# IO_Converter.net
KiCad netlist of a schematic drawn in Altium Designer
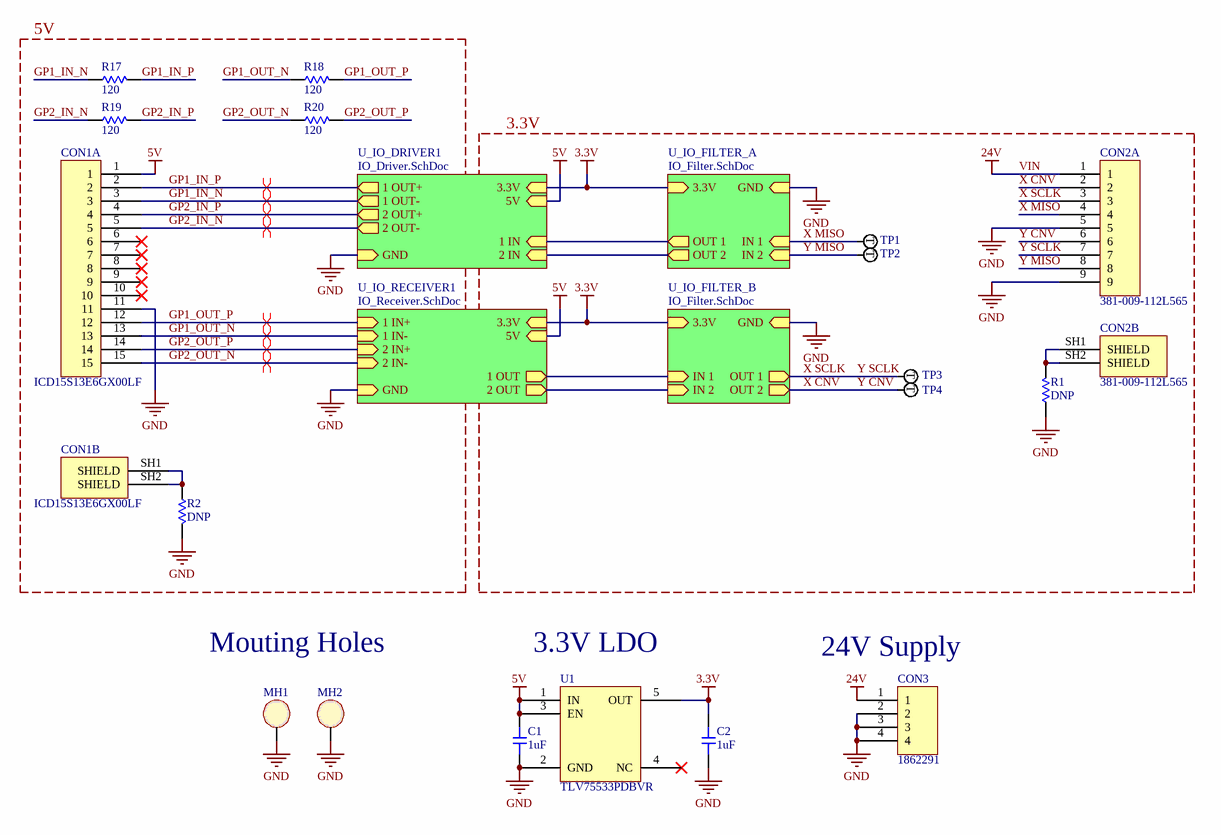
[diagram p0: IO_Converter.SchDoc]

(export (version "E")
  (design (tool "Eeschema 10.0.6"))
  (components
    (comp (ref "C1")
      (value "1uF")
      (footprint "0603-CAP")
      (description "CAP CER 1UF 10V X5R 0603")
      (fields (field (name "Comment") "CL10A105KP8NNWC"))
      (libsource (lib "IO_Converter") (part "Capacitor 1uF"))
    )
    (comp (ref "C2")
      (value "1uF")
      (footprint "0603-CAP")
      (description "CAP CER 1UF 10V X5R 0603")
      (fields (field (name "Comment") "CL10A105KP8NNWC"))
      (libsource (lib "IO_Converter") (part "Capacitor 1uF"))
    )
    (comp (ref "CON1")
      (value "ICD15S13E6GX00LF")
      (footprint "ICD15S13E6GX00LF")
      (description "15 Position D-Sub, High Density Receptacle, Female Sockets Connector")
      (libsource (lib "CRAMB") (part "ICD15S13E6GX00LF"))
    )
    (comp (ref "CON2")
      (value "381-009-112L565")
      (footprint "381-009-112L565")
      (description "9 Position D-Type, Micro-D Plug, Male Pins Connector")
      (libsource (lib "IO_Converter") (part "381-009-112L565"))
    )
    (comp (ref "CON3")
      (value "1862291")
      (footprint "1862291")
      (description "TERM BLOCK 4POS 45DEG 5MM PCB")
      (libsource (lib "IO_Converter") (part "1862291"))
    )
    (comp (ref "MH1")
      (value "MOUNT_HOLE")
      (footprint "MOUNTING_HOLE")
      (description "MOUNTING HOLE")
      (libsource (lib "IO_Converter") (part "MOUNT_HOLE"))
    )
    (comp (ref "MH2")
      (value "MOUNT_HOLE")
      (footprint "MOUNTING_HOLE")
      (description "MOUNTING HOLE")
      (libsource (lib "IO_Converter") (part "MOUNT_HOLE"))
    )
    (comp (ref "R1")
      (value "DNP")
      (footprint "0603-RES")
      (fields (field (name "Comment") "Resistor"))
      (libsource (lib "CRAMB") (part "Resistor"))
    )
    (comp (ref "R2")
      (value "DNP")
      (footprint "0603-RES")
      (fields (field (name "Comment") "Resistor"))
      (libsource (lib "CRAMB") (part "Resistor"))
    )
    (comp (ref "R17")
      (value "120")
      (footprint "0603-RES")
      (description "RES 120 OHM 5% 1/10W 0603")
      (fields (field (name "MANUFACTURER PART NUMBER") "RMCF0603JT120R"))
      (libsource (lib "IO_Converter") (part "Resistor"))
    )
    (comp (ref "R18")
      (value "120")
      (footprint "0603-RES")
      (description "RES 120 OHM 5% 1/10W 0603")
      (fields (field (name "MANUFACTURER PART NUMBER") "RMCF0603JT120R"))
      (libsource (lib "IO_Converter") (part "Resistor"))
    )
    (comp (ref "R19")
      (value "120")
      (footprint "0603-RES")
      (description "RES 120 OHM 5% 1/10W 0603")
      (fields (field (name "MANUFACTURER PART NUMBER") "RMCF0603JT120R"))
      (libsource (lib "IO_Converter") (part "Resistor"))
    )
    (comp (ref "R20")
      (value "120")
      (footprint "0603-RES")
      (description "RES 120 OHM 5% 1/10W 0603")
      (fields (field (name "Comment") "RMCF0603JT120R"))
      (libsource (lib "IO_Converter") (part "Resistor"))
    )
    (comp (ref "TP1")
      (value "RCU-0C")
      (footprint "RCU-0C")
      (description "PC TEST POINT NATURAL")
      (libsource (lib "IO_Converter") (part "Test Point"))
    )
    (comp (ref "TP2")
      (value "RCU-0C")
      (footprint "RCU-0C")
      (description "PC TEST POINT NATURAL")
      (libsource (lib "IO_Converter") (part "Test Point"))
    )
    (comp (ref "TP3")
      (value "RCU-0C")
      (footprint "RCU-0C")
      (description "PC TEST POINT NATURAL")
      (libsource (lib "IO_Converter") (part "Test Point"))
    )
    (comp (ref "TP4")
      (value "RCU-0C")
      (footprint "RCU-0C")
      (description "PC TEST POINT NATURAL")
      (libsource (lib "IO_Converter") (part "Test Point"))
    )
    (comp (ref "U1")
      (value "TLV75533PDBVR")
      (footprint "SOT95P280X145-5N")
      (description "IC REG LINEAR 3.3V 500MA SOT23-5")
      (libsource (lib "IO_Converter") (part "TLV75533PDBVR"))
    )
  )
  (nets
    (net (code "3") (name "/GP1_IN_N") (class "Default")
      (node (ref "CON1") (pin "3") (pinfunction "3_3") (pintype "passive"))
      (node (ref "R17") (pin "1") (pinfunction "1_1") (pintype "passive"))
    )
    (net (code "4") (name "/GP1_IN_P") (class "Default")
      (node (ref "CON1") (pin "2") (pinfunction "2_2") (pintype "passive"))
      (node (ref "R17") (pin "2") (pinfunction "2_2") (pintype "passive"))
    )
    (net (code "5") (name "/GP1_OUT_N") (class "Default")
      (node (ref "CON1") (pin "13") (pinfunction "13_13") (pintype "passive"))
      (node (ref "R18") (pin "1") (pinfunction "1_1") (pintype "passive"))
    )
    (net (code "6") (name "/GP1_OUT_P") (class "Default")
      (node (ref "CON1") (pin "12") (pinfunction "12_12") (pintype "passive"))
      (node (ref "R18") (pin "2") (pinfunction "2_2") (pintype "passive"))
    )
    (net (code "7") (name "/GP2_IN_N") (class "Default")
      (node (ref "CON1") (pin "5") (pinfunction "5_5") (pintype "passive"))
      (node (ref "R19") (pin "1") (pinfunction "1_1") (pintype "passive"))
    )
    (net (code "8") (name "/GP2_IN_P") (class "Default")
      (node (ref "CON1") (pin "4") (pinfunction "4_4") (pintype "passive"))
      (node (ref "R19") (pin "2") (pinfunction "2_2") (pintype "passive"))
    )
    (net (code "9") (name "/GP2_OUT_N") (class "Default")
      (node (ref "CON1") (pin "15") (pinfunction "15_15") (pintype "passive"))
      (node (ref "R20") (pin "1") (pinfunction "1_1") (pintype "passive"))
    )
    (net (code "10") (name "/GP2_OUT_P") (class "Default")
      (node (ref "CON1") (pin "14") (pinfunction "14_14") (pintype "passive"))
      (node (ref "R20") (pin "2") (pinfunction "2_2") (pintype "passive"))
    )
    (net (code "13") (name "/X CNV") (class "Default")
      (node (ref "CON2") (pin "2") (pinfunction "2_2") (pintype "passive"))
      (node (ref "CON2") (pin "6") (pinfunction "6_6") (pintype "passive"))
      (node (ref "TP4") (pin "1") (pinfunction "1_1") (pintype "passive"))
    )
    (net (code "14") (name "/X MISO") (class "Default")
      (node (ref "CON2") (pin "4") (pinfunction "4_4") (pintype "passive"))
      (node (ref "TP1") (pin "1") (pinfunction "1_1") (pintype "passive"))
    )
    (net (code "15") (name "/X SCLK") (class "Default")
      (node (ref "CON2") (pin "3") (pinfunction "3_3") (pintype "passive"))
      (node (ref "CON2") (pin "7") (pinfunction "7_7") (pintype "passive"))
      (node (ref "TP3") (pin "1") (pinfunction "1_1") (pintype "passive"))
    )
    (net (code "16") (name "/Y MISO") (class "Default")
      (node (ref "CON2") (pin "8") (pinfunction "8_8") (pintype "passive"))
      (node (ref "TP2") (pin "1") (pinfunction "1_1") (pintype "passive"))
    )
    (net (code "17") (name "3.3V") (class "Default")
      (node (ref "C2") (pin "2") (pinfunction "2_2") (pintype "passive"))
      (node (ref "U1") (pin "5") (pinfunction "OUT_5") (pintype "passive"))
    )
    (net (code "18") (name "5V") (class "Default")
      (node (ref "C1") (pin "2") (pinfunction "2_2") (pintype "passive"))
      (node (ref "CON1") (pin "1") (pinfunction "1_1") (pintype "passive"))
      (node (ref "U1") (pin "1") (pinfunction "IN_1") (pintype "passive"))
      (node (ref "U1") (pin "3") (pinfunction "EN_3") (pintype "passive"))
    )
    (net (code "19") (name "24V") (class "Default")
      (node (ref "CON2") (pin "1") (pinfunction "1_1") (pintype "passive"))
      (node (ref "CON3") (pin "1") (pinfunction "1_1") (pintype "passive"))
    )
    (net (code "20") (name "GND") (class "Default")
      (node (ref "C1") (pin "1") (pinfunction "1_1") (pintype "passive"))
      (node (ref "C2") (pin "1") (pinfunction "1_1") (pintype "passive"))
      (node (ref "CON1") (pin "11") (pinfunction "11_11") (pintype "passive"))
      (node (ref "CON2") (pin "5") (pinfunction "5_5") (pintype "passive"))
      (node (ref "CON2") (pin "9") (pinfunction "9_9") (pintype "passive"))
      (node (ref "CON3") (pin "2") (pinfunction "2_2") (pintype "passive"))
      (node (ref "CON3") (pin "3") (pinfunction "3_3") (pintype "passive"))
      (node (ref "CON3") (pin "4") (pinfunction "4_4") (pintype "passive"))
      (node (ref "MH1") (pin "1") (pinfunction "1_1") (pintype "passive"))
      (node (ref "MH2") (pin "1") (pinfunction "1_1") (pintype "passive"))
      (node (ref "R1") (pin "2") (pinfunction "2_2") (pintype "passive"))
      (node (ref "R2") (pin "2") (pinfunction "2_2") (pintype "passive"))
      (node (ref "U1") (pin "2") (pinfunction "GND_2") (pintype "passive"))
    )
    (net (code "21") (name "Net-(CON1B-SHIELD-PadSH1)") (class "Default")
      (node (ref "CON1") (pin "SH1") (pinfunction "SHIELD_SH1") (pintype "passive"))
      (node (ref "CON1") (pin "SH2") (pinfunction "SHIELD_SH2") (pintype "passive"))
      (node (ref "R2") (pin "1") (pinfunction "1_1") (pintype "passive"))
    )
    (net (code "22") (name "Net-(CON2B-SHIELD-PadSH1)") (class "Default")
      (node (ref "CON2") (pin "SH1") (pinfunction "SHIELD_SH1") (pintype "passive"))
      (node (ref "CON2") (pin "SH2") (pinfunction "SHIELD_SH2") (pintype "passive"))
      (node (ref "R1") (pin "1") (pinfunction "1_1") (pintype "passive"))
    )
    (net (code "23") (name "unconnected-(CON1-Pad6)") (class "Default")
      (node (ref "CON1") (pin "6") (pinfunction "6_6") (pintype "passive+no_connect"))
    )
    (net (code "24") (name "unconnected-(CON1-Pad7)") (class "Default")
      (node (ref "CON1") (pin "7") (pinfunction "7_7") (pintype "passive+no_connect"))
    )
    (net (code "25") (name "unconnected-(CON1-Pad8)") (class "Default")
      (node (ref "CON1") (pin "8") (pinfunction "8_8") (pintype "passive+no_connect"))
    )
    (net (code "26") (name "unconnected-(CON1-Pad9)") (class "Default")
      (node (ref "CON1") (pin "9") (pinfunction "9_9") (pintype "passive+no_connect"))
    )
    (net (code "27") (name "unconnected-(CON1-Pad10)") (class "Default")
      (node (ref "CON1") (pin "10") (pinfunction "10_10") (pintype "passive+no_connect"))
    )
    (net (code "28") (name "unconnected-(U1-NC-Pad4)") (class "Default")
      (node (ref "U1") (pin "4") (pinfunction "NC_4") (pintype "passive+no_connect"))
    )
  )
)
